# RTM_SFP_TOP.net
KiCad netlist of a schematic drawn in Altium Designer
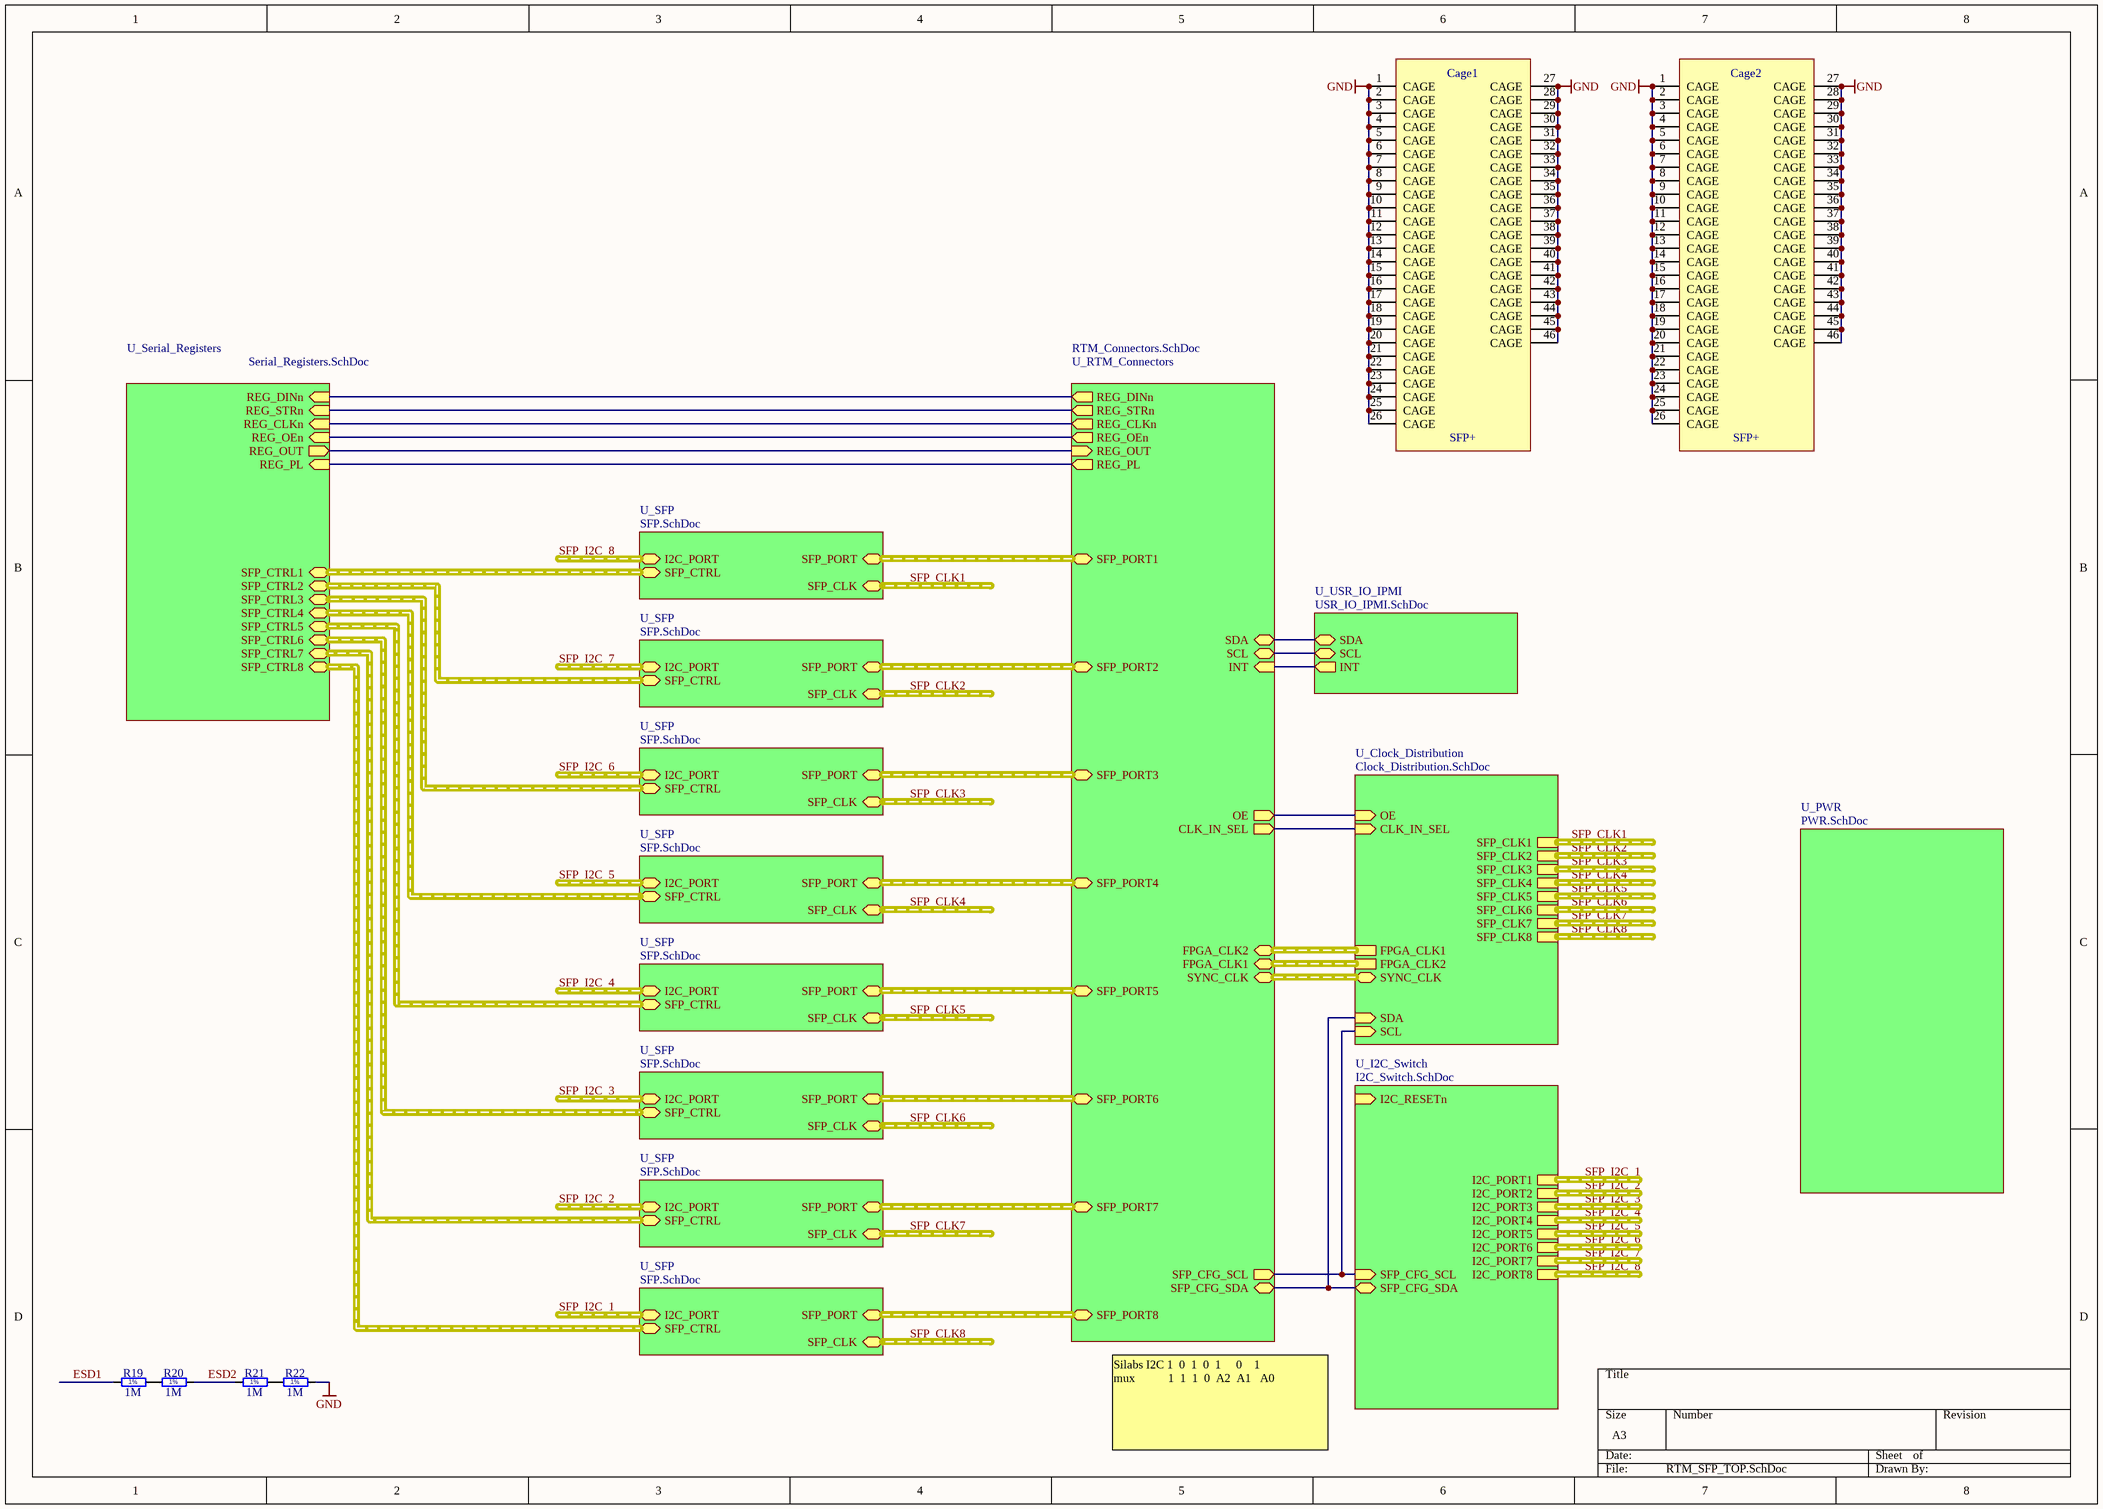
[diagram p0: RTM_SFP_TOP.SchDoc]

(export (version "E")
  (design (tool "Eeschema 10.0.6"))
  (components
    (comp (ref "Cage1")
      (value "SFP+")
      (footprint "TYCO_2007132-1")
      (description "SFP+  1x4 Cage (46 Pins)")
      (fields
        (field (name "PART NUMBER") "TYCO_2007132-1")
        (field (name "MANUFACTURER") "TYCO ELECTRONICS")
        (field (name "AUTHOR") "CERN DEM JLC")
      )
      (libsource (lib "Connectors") (part "SFP+ 1x4 Cage (46Pins)"))
    )
    (comp (ref "Cage2")
      (value "SFP+")
      (footprint "TYCO_2007132-1")
      (description "SFP+  1x4 Cage (46 Pins)")
      (fields
        (field (name "PART NUMBER") "TYCO_2007132-1")
        (field (name "MANUFACTURER") "TYCO ELECTRONICS")
        (field (name "AUTHOR") "CERN DEM JLC")
      )
      (libsource (lib "Connectors") (part "SFP+ 1x4 Cage (46Pins)"))
    )
    (comp (ref "R19")
      (value "1M")
      (footprint "RESC3216X65N")
      (description "Resistor - 1%")
      (fields
        (field (name "PART NUMBER") "R1206_1M_1%_0.25W_100PPM")
        (field (name "POWER") "0.25W")
        (field (name "AUTHOR") "CERN DEM JLC")
      )
      (libsource (lib "Resistors") (part "Resistor - 1%"))
    )
    (comp (ref "R20")
      (value "1M")
      (footprint "RESC3216X65N")
      (description "Resistor - 1%")
      (fields
        (field (name "PART NUMBER") "R1206_1M_1%_0.25W_100PPM")
        (field (name "POWER") "0.25W")
        (field (name "AUTHOR") "CERN DEM JLC")
      )
      (libsource (lib "Resistors") (part "Resistor - 1%"))
    )
    (comp (ref "R21")
      (value "1M")
      (footprint "RESC3216X65N")
      (description "Resistor - 1%")
      (fields
        (field (name "PART NUMBER") "R1206_1M_1%_0.25W_100PPM")
        (field (name "POWER") "0.25W")
        (field (name "AUTHOR") "CERN DEM JLC")
      )
      (libsource (lib "Resistors") (part "Resistor - 1%"))
    )
    (comp (ref "R22")
      (value "1M")
      (footprint "RESC3216X65N")
      (description "Resistor - 1%")
      (fields
        (field (name "PART NUMBER") "R1206_1M_1%_0.25W_100PPM")
        (field (name "POWER") "0.25W")
        (field (name "AUTHOR") "CERN DEM JLC")
      )
      (libsource (lib "Resistors") (part "Resistor - 1%"))
    )
  )
  (nets
    (net (code "18") (name "/ESD1") (class "Default")
      (node (ref "R19") (pin "1") (pinfunction "1_1") (pintype "passive"))
    )
    (net (code "19") (name "/ESD2") (class "Default")
      (node (ref "R20") (pin "2") (pinfunction "2_2") (pintype "passive"))
      (node (ref "R21") (pin "1") (pinfunction "1_1") (pintype "passive"))
    )
    (net (code "68") (name "GND") (class "Default")
      (node (ref "Cage1") (pin "1") (pinfunction "CAGE_1") (pintype "power_in"))
      (node (ref "Cage1") (pin "10") (pinfunction "CAGE_10") (pintype "power_in"))
      (node (ref "Cage1") (pin "11") (pinfunction "CAGE_11") (pintype "power_in"))
      (node (ref "Cage1") (pin "12") (pinfunction "CAGE_12") (pintype "power_in"))
      (node (ref "Cage1") (pin "13") (pinfunction "CAGE_13") (pintype "power_in"))
      (node (ref "Cage1") (pin "14") (pinfunction "CAGE_14") (pintype "power_in"))
      (node (ref "Cage1") (pin "15") (pinfunction "CAGE_15") (pintype "power_in"))
      (node (ref "Cage1") (pin "16") (pinfunction "CAGE_16") (pintype "power_in"))
      (node (ref "Cage1") (pin "17") (pinfunction "CAGE_17") (pintype "power_in"))
      (node (ref "Cage1") (pin "18") (pinfunction "CAGE_18") (pintype "power_in"))
      (node (ref "Cage1") (pin "19") (pinfunction "CAGE_19") (pintype "power_in"))
      (node (ref "Cage1") (pin "2") (pinfunction "CAGE_2") (pintype "power_in"))
      (node (ref "Cage1") (pin "20") (pinfunction "CAGE_20") (pintype "power_in"))
      (node (ref "Cage1") (pin "21") (pinfunction "CAGE_21") (pintype "power_in"))
      (node (ref "Cage1") (pin "22") (pinfunction "CAGE_22") (pintype "power_in"))
      (node (ref "Cage1") (pin "23") (pinfunction "CAGE_23") (pintype "power_in"))
      (node (ref "Cage1") (pin "24") (pinfunction "CAGE_24") (pintype "power_in"))
      (node (ref "Cage1") (pin "25") (pinfunction "CAGE_25") (pintype "power_in"))
      (node (ref "Cage1") (pin "26") (pinfunction "CAGE_26") (pintype "power_in"))
      (node (ref "Cage1") (pin "27") (pinfunction "CAGE_27") (pintype "power_in"))
      (node (ref "Cage1") (pin "28") (pinfunction "CAGE_28") (pintype "power_in"))
      (node (ref "Cage1") (pin "29") (pinfunction "CAGE_29") (pintype "power_in"))
      (node (ref "Cage1") (pin "3") (pinfunction "CAGE_3") (pintype "power_in"))
      (node (ref "Cage1") (pin "30") (pinfunction "CAGE_30") (pintype "power_in"))
      (node (ref "Cage1") (pin "31") (pinfunction "CAGE_31") (pintype "power_in"))
      (node (ref "Cage1") (pin "32") (pinfunction "CAGE_32") (pintype "power_in"))
      (node (ref "Cage1") (pin "33") (pinfunction "CAGE_33") (pintype "power_in"))
      (node (ref "Cage1") (pin "34") (pinfunction "CAGE_34") (pintype "power_in"))
      (node (ref "Cage1") (pin "35") (pinfunction "CAGE_35") (pintype "power_in"))
      (node (ref "Cage1") (pin "36") (pinfunction "CAGE_36") (pintype "power_in"))
      (node (ref "Cage1") (pin "37") (pinfunction "CAGE_37") (pintype "power_in"))
      (node (ref "Cage1") (pin "38") (pinfunction "CAGE_38") (pintype "power_in"))
      (node (ref "Cage1") (pin "39") (pinfunction "CAGE_39") (pintype "power_in"))
      (node (ref "Cage1") (pin "4") (pinfunction "CAGE_4") (pintype "power_in"))
      (node (ref "Cage1") (pin "40") (pinfunction "CAGE_40") (pintype "power_in"))
      (node (ref "Cage1") (pin "41") (pinfunction "CAGE_41") (pintype "power_in"))
      (node (ref "Cage1") (pin "42") (pinfunction "CAGE_42") (pintype "power_in"))
      (node (ref "Cage1") (pin "43") (pinfunction "CAGE_43") (pintype "power_in"))
      (node (ref "Cage1") (pin "44") (pinfunction "CAGE_44") (pintype "power_in"))
      (node (ref "Cage1") (pin "45") (pinfunction "CAGE_45") (pintype "power_in"))
      (node (ref "Cage1") (pin "46") (pinfunction "CAGE_46") (pintype "power_in"))
      (node (ref "Cage1") (pin "5") (pinfunction "CAGE_5") (pintype "power_in"))
      (node (ref "Cage1") (pin "6") (pinfunction "CAGE_6") (pintype "power_in"))
      (node (ref "Cage1") (pin "7") (pinfunction "CAGE_7") (pintype "power_in"))
      (node (ref "Cage1") (pin "8") (pinfunction "CAGE_8") (pintype "power_in"))
      (node (ref "Cage1") (pin "9") (pinfunction "CAGE_9") (pintype "power_in"))
      (node (ref "Cage2") (pin "1") (pinfunction "CAGE_1") (pintype "power_in"))
      (node (ref "Cage2") (pin "10") (pinfunction "CAGE_10") (pintype "power_in"))
      (node (ref "Cage2") (pin "11") (pinfunction "CAGE_11") (pintype "power_in"))
      (node (ref "Cage2") (pin "12") (pinfunction "CAGE_12") (pintype "power_in"))
      (node (ref "Cage2") (pin "13") (pinfunction "CAGE_13") (pintype "power_in"))
      (node (ref "Cage2") (pin "14") (pinfunction "CAGE_14") (pintype "power_in"))
      (node (ref "Cage2") (pin "15") (pinfunction "CAGE_15") (pintype "power_in"))
      (node (ref "Cage2") (pin "16") (pinfunction "CAGE_16") (pintype "power_in"))
      (node (ref "Cage2") (pin "17") (pinfunction "CAGE_17") (pintype "power_in"))
      (node (ref "Cage2") (pin "18") (pinfunction "CAGE_18") (pintype "power_in"))
      (node (ref "Cage2") (pin "19") (pinfunction "CAGE_19") (pintype "power_in"))
      (node (ref "Cage2") (pin "2") (pinfunction "CAGE_2") (pintype "power_in"))
      (node (ref "Cage2") (pin "20") (pinfunction "CAGE_20") (pintype "power_in"))
      (node (ref "Cage2") (pin "21") (pinfunction "CAGE_21") (pintype "power_in"))
      (node (ref "Cage2") (pin "22") (pinfunction "CAGE_22") (pintype "power_in"))
      (node (ref "Cage2") (pin "23") (pinfunction "CAGE_23") (pintype "power_in"))
      (node (ref "Cage2") (pin "24") (pinfunction "CAGE_24") (pintype "power_in"))
      (node (ref "Cage2") (pin "25") (pinfunction "CAGE_25") (pintype "power_in"))
      (node (ref "Cage2") (pin "26") (pinfunction "CAGE_26") (pintype "power_in"))
      (node (ref "Cage2") (pin "27") (pinfunction "CAGE_27") (pintype "power_in"))
      (node (ref "Cage2") (pin "28") (pinfunction "CAGE_28") (pintype "power_in"))
      (node (ref "Cage2") (pin "29") (pinfunction "CAGE_29") (pintype "power_in"))
      (node (ref "Cage2") (pin "3") (pinfunction "CAGE_3") (pintype "power_in"))
      (node (ref "Cage2") (pin "30") (pinfunction "CAGE_30") (pintype "power_in"))
      (node (ref "Cage2") (pin "31") (pinfunction "CAGE_31") (pintype "power_in"))
      (node (ref "Cage2") (pin "32") (pinfunction "CAGE_32") (pintype "power_in"))
      (node (ref "Cage2") (pin "33") (pinfunction "CAGE_33") (pintype "power_in"))
      (node (ref "Cage2") (pin "34") (pinfunction "CAGE_34") (pintype "power_in"))
      (node (ref "Cage2") (pin "35") (pinfunction "CAGE_35") (pintype "power_in"))
      (node (ref "Cage2") (pin "36") (pinfunction "CAGE_36") (pintype "power_in"))
      (node (ref "Cage2") (pin "37") (pinfunction "CAGE_37") (pintype "power_in"))
      (node (ref "Cage2") (pin "38") (pinfunction "CAGE_38") (pintype "power_in"))
      (node (ref "Cage2") (pin "39") (pinfunction "CAGE_39") (pintype "power_in"))
      (node (ref "Cage2") (pin "4") (pinfunction "CAGE_4") (pintype "power_in"))
      (node (ref "Cage2") (pin "40") (pinfunction "CAGE_40") (pintype "power_in"))
      (node (ref "Cage2") (pin "41") (pinfunction "CAGE_41") (pintype "power_in"))
      (node (ref "Cage2") (pin "42") (pinfunction "CAGE_42") (pintype "power_in"))
      (node (ref "Cage2") (pin "43") (pinfunction "CAGE_43") (pintype "power_in"))
      (node (ref "Cage2") (pin "44") (pinfunction "CAGE_44") (pintype "power_in"))
      (node (ref "Cage2") (pin "45") (pinfunction "CAGE_45") (pintype "power_in"))
      (node (ref "Cage2") (pin "46") (pinfunction "CAGE_46") (pintype "power_in"))
      (node (ref "Cage2") (pin "5") (pinfunction "CAGE_5") (pintype "power_in"))
      (node (ref "Cage2") (pin "6") (pinfunction "CAGE_6") (pintype "power_in"))
      (node (ref "Cage2") (pin "7") (pinfunction "CAGE_7") (pintype "power_in"))
      (node (ref "Cage2") (pin "8") (pinfunction "CAGE_8") (pintype "power_in"))
      (node (ref "Cage2") (pin "9") (pinfunction "CAGE_9") (pintype "power_in"))
      (node (ref "R22") (pin "2") (pinfunction "2_2") (pintype "passive"))
    )
    (net (code "69") (name "Net-(R19-Pad2)") (class "Default")
      (node (ref "R19") (pin "2") (pinfunction "2_2") (pintype "passive"))
      (node (ref "R20") (pin "1") (pinfunction "1_1") (pintype "passive"))
    )
    (net (code "70") (name "Net-(R21-Pad2)") (class "Default")
      (node (ref "R21") (pin "2") (pinfunction "2_2") (pintype "passive"))
      (node (ref "R22") (pin "1") (pinfunction "1_1") (pintype "passive"))
    )
  )
)
